# HPF_20Hz.net
KiCad netlist of a schematic drawn in Altium Designer
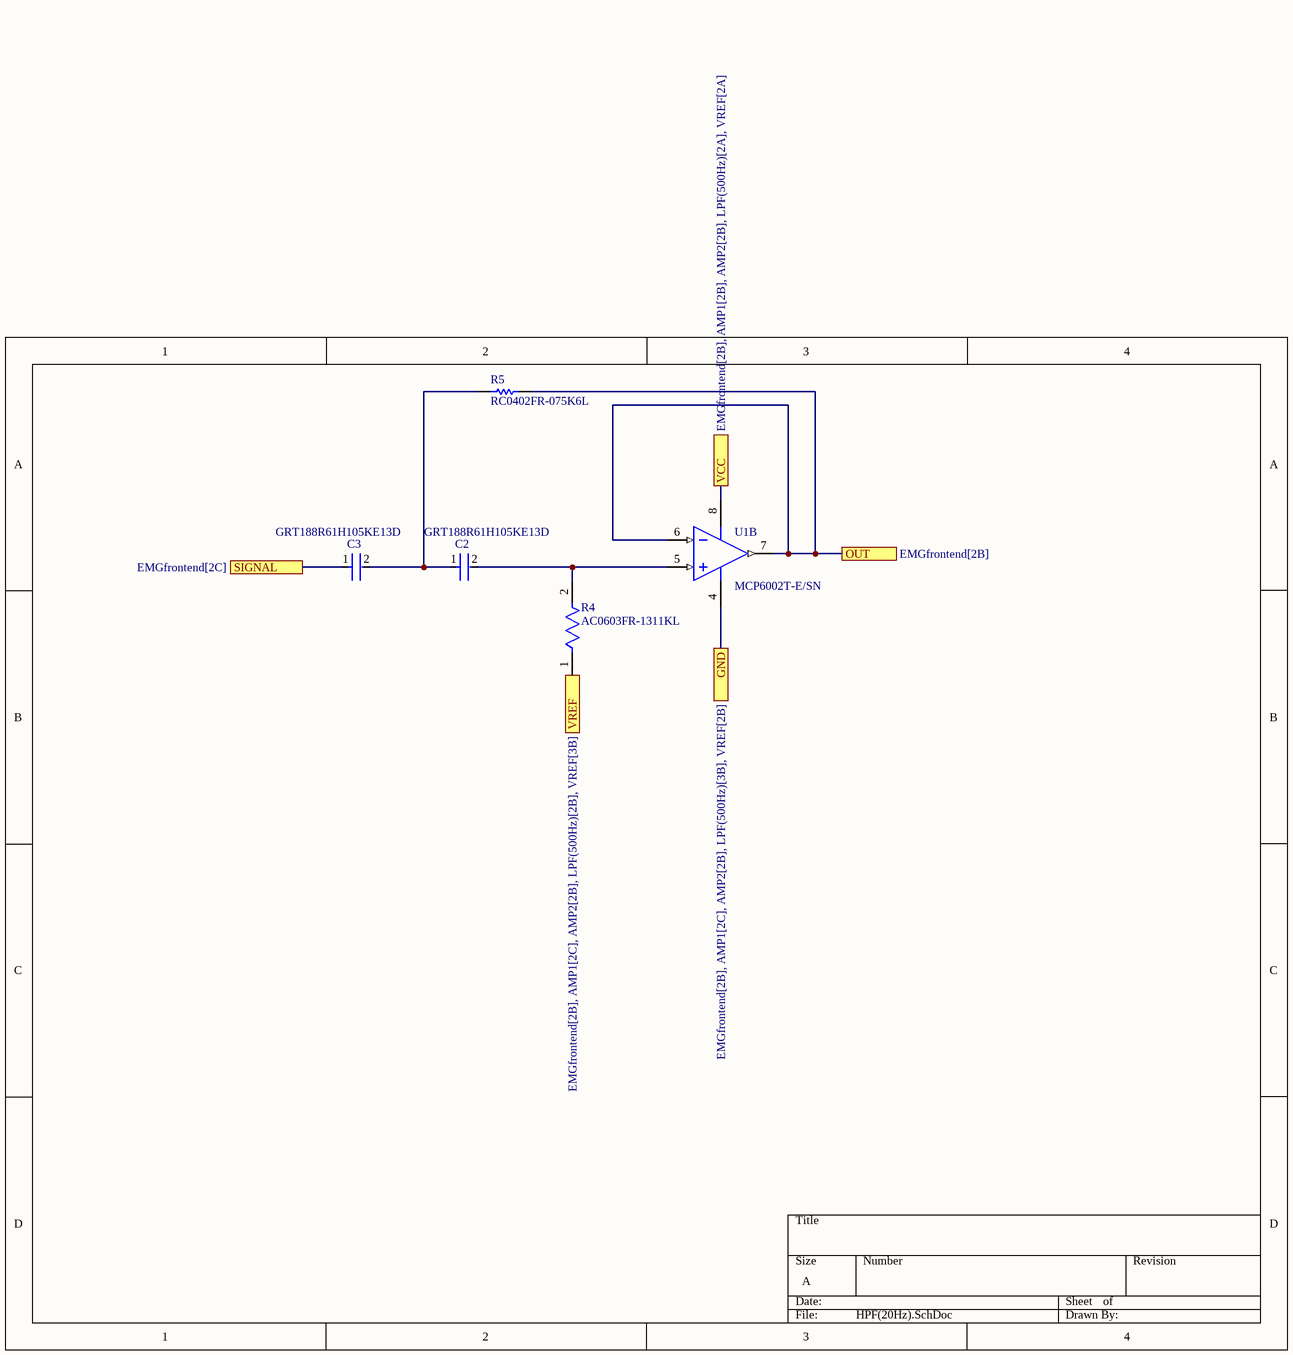
[diagram p0: HPF(20Hz).SchDoc]

(export (version "E")
  (design (tool "Eeschema 10.0.6"))
  (components
    (comp (ref "C2")
      (value "GRT188R61H105KE13D")
      (footprint "FP-GRT188-0_1-e0_2_0_5-IPC_B")
      (description "Multi-Layer Ceramic Capacitor 1uF 50V X5R ±10% 0603 Paper T/R")
      (fields (field (name "TOLERANCE") "10%"))
      (libsource (lib "Altium Content Vault") (part "02cd4be3c70576c341d710602a673aa"))
    )
    (comp (ref "C3")
      (value "GRT188R61H105KE13D")
      (footprint "FP-GRT188-0_1-e0_2_0_5-IPC_B")
      (description "Multi-Layer Ceramic Capacitor 1uF 50V X5R ±10% 0603 Paper T/R")
      (fields (field (name "TOLERANCE") "10%"))
      (libsource (lib "Altium Content Vault") (part "02cd4be3c70576c341d710602a673aa"))
    )
    (comp (ref "R4")
      (value "AC0603FR-1311KL")
      (footprint "FP-AC0603-IPC_B")
      (description "RES 11KΩ 1.00% 0.1W 0603")
      (libsource (lib "Altium Content Vault") (part "1029c3af85768c4190bb7ad29bc67b5"))
    )
    (comp (ref "R5")
      (value "RC0402FR-075K6L")
      (footprint "RESC1005X40X25LL05T10")
      (fields (field (name "MANUFACTURER") "Yageo / Phycomp"))
      (libsource (lib "Altium Content Vault") (part "RES"))
    )
    (comp (ref "U1")
      (value "MCP6002T-E/SN")
      (footprint "SOIC-SN8_N")
      (description "None")
      (libsource (lib "Altium Content Vault") (part "AMP-OPA-MCP6002-IL8"))
    )
  )
  (nets
    (net (code "1") (name "/GND") (class "Default")
      (node (ref "U1") (pin "4") (pinfunction "VSS_4") (pintype "power_in"))
    )
    (net (code "2") (name "/OUT") (class "Default")
      (node (ref "R5") (pin "2") (pinfunction "2_2") (pintype "passive"))
      (node (ref "U1") (pin "6") (pinfunction "VINB-_6") (pintype "input"))
      (node (ref "U1") (pin "7") (pinfunction "VOUTB_7") (pintype "output"))
    )
    (net (code "3") (name "/SIGNAL") (class "Default")
      (node (ref "C3") (pin "1") (pinfunction "1_1") (pintype "passive"))
    )
    (net (code "4") (name "/VCC") (class "Default")
      (node (ref "U1") (pin "8") (pinfunction "VDD_8") (pintype "power_in"))
    )
    (net (code "5") (name "/VREF") (class "Default")
      (node (ref "R4") (pin "1") (pinfunction "1_1") (pintype "passive"))
    )
    (net (code "6") (name "Net-(C2-Pad1)") (class "Default")
      (node (ref "C2") (pin "1") (pinfunction "1_1") (pintype "passive"))
      (node (ref "C3") (pin "2") (pinfunction "2_2") (pintype "passive"))
      (node (ref "R5") (pin "1") (pinfunction "1_1") (pintype "passive"))
    )
    (net (code "7") (name "Net-(U1B-VINB+)") (class "Default")
      (node (ref "C2") (pin "2") (pinfunction "2_2") (pintype "passive"))
      (node (ref "R4") (pin "2") (pinfunction "2_2") (pintype "passive"))
      (node (ref "U1") (pin "5") (pinfunction "VINB+_5") (pintype "input"))
    )
  )
)
